# evlogger_voltage.net
KiCad netlist of a schematic drawn in EAGLE
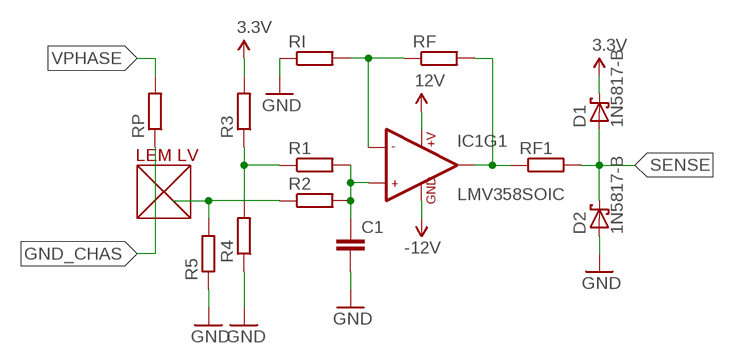
[diagram p0: schematic, sheet 1]

(export (version "E")
  (design (tool "Eeschema 10.0.6"))
  (components
    (comp (ref "C1")
      (value "C-EU025-024X044")
      (footprint "eagle-import:C025-024X044")
      (libsource (lib "eagle-import") (part "C-EU025-024X044"))
    )
    (comp (ref "D1")
      (value "1N5817-B")
      (footprint "eagle-import:DO41-7.6")
      (libsource (lib "eagle-import") (part "1N5817-B"))
    )
    (comp (ref "D2")
      (value "1N5817-B")
      (footprint "eagle-import:DO41-7.6")
      (libsource (lib "eagle-import") (part "1N5817-B"))
    )
    (comp (ref "IC1")
      (value "LMV358SOIC")
      (footprint "eagle-import:SO08")
      (libsource (lib "eagle-import") (part "LMV358SOIC"))
    )
    (comp (ref "R1")
      (value "R-EU_0207/10")
      (footprint "eagle-import:0207_10")
      (libsource (lib "eagle-import") (part "R-EU_0207/10"))
    )
    (comp (ref "R2")
      (value "R-EU_0207/10")
      (footprint "eagle-import:0207_10")
      (libsource (lib "eagle-import") (part "R-EU_0207/10"))
    )
    (comp (ref "R3")
      (value "R-EU_0207/10")
      (footprint "eagle-import:0207_10")
      (libsource (lib "eagle-import") (part "R-EU_0207/10"))
    )
    (comp (ref "R4")
      (value "R-EU_0207/10")
      (footprint "eagle-import:0207_10")
      (libsource (lib "eagle-import") (part "R-EU_0207/10"))
    )
    (comp (ref "R5")
      (value "R-EU_0207/10")
      (footprint "eagle-import:0207_10")
      (libsource (lib "eagle-import") (part "R-EU_0207/10"))
    )
    (comp (ref "RF")
      (value "R-EU_0207/10")
      (footprint "eagle-import:0207_10")
      (libsource (lib "eagle-import") (part "R-EU_0207/10"))
    )
    (comp (ref "RF1")
      (value "R-EU_0207/10")
      (footprint "eagle-import:0207_10")
      (libsource (lib "eagle-import") (part "R-EU_0207/10"))
    )
    (comp (ref "RI")
      (value "R-EU_0207/10")
      (footprint "eagle-import:0207_10")
      (libsource (lib "eagle-import") (part "R-EU_0207/10"))
    )
    (comp (ref "RP")
      (value "R-EU_0207/10")
      (footprint "eagle-import:0207_10")
      (libsource (lib "eagle-import") (part "R-EU_0207/10"))
    )
  )
  (nets
    (net (code "1") (name "-12V") (class "Default")
      (node (ref "IC1") (pin "4") (pinfunction "GND_4") (pintype "power_in"))
    )
    (net (code "2") (name "3.3V") (class "Default")
      (node (ref "D1") (pin "C") (pinfunction "C_C") (pintype "passive"))
      (node (ref "R3") (pin "2") (pinfunction "2_2") (pintype "passive"))
    )
    (net (code "3") (name "12V") (class "Default")
      (node (ref "IC1") (pin "8") (pinfunction "+V_8") (pintype "power_in"))
    )
    (net (code "4") (name "GND") (class "Default")
      (node (ref "C1") (pin "2") (pinfunction "2_2") (pintype "passive"))
      (node (ref "D2") (pin "A") (pinfunction "A_A") (pintype "passive"))
      (node (ref "R4") (pin "1") (pinfunction "1_1") (pintype "passive"))
      (node (ref "R5") (pin "1") (pinfunction "1_1") (pintype "passive"))
      (node (ref "RI") (pin "1") (pinfunction "1_1") (pintype "passive"))
    )
    (net (code "5") (name "GND_CHAS") (class "Default")
      (node (ref "RP") (pin "1") (pinfunction "1_1") (pintype "passive"))
    )
    (net (code "6") (name "Net-(IC1A-+IN1)") (class "Default")
      (node (ref "C1") (pin "1") (pinfunction "1_1") (pintype "passive"))
      (node (ref "IC1") (pin "3") (pinfunction "+IN1_3") (pintype "input"))
      (node (ref "R1") (pin "2") (pinfunction "2_2") (pintype "passive"))
      (node (ref "R2") (pin "2") (pinfunction "2_2") (pintype "passive"))
    )
    (net (code "7") (name "Net-(IC1A--IN1)") (class "Default")
      (node (ref "IC1") (pin "2") (pinfunction "-IN1_2") (pintype "input"))
      (node (ref "RF") (pin "1") (pinfunction "1_1") (pintype "passive"))
      (node (ref "RI") (pin "2") (pinfunction "2_2") (pintype "passive"))
    )
    (net (code "8") (name "Net-(IC1A-OUT1)") (class "Default")
      (node (ref "IC1") (pin "1") (pinfunction "OUT1_1") (pintype "output"))
      (node (ref "RF") (pin "2") (pinfunction "2_2") (pintype "passive"))
      (node (ref "RF1") (pin "1") (pinfunction "1_1") (pintype "passive"))
    )
    (net (code "9") (name "Net-(R1-Pad1)") (class "Default")
      (node (ref "R1") (pin "1") (pinfunction "1_1") (pintype "passive"))
      (node (ref "R3") (pin "1") (pinfunction "1_1") (pintype "passive"))
      (node (ref "R4") (pin "2") (pinfunction "2_2") (pintype "passive"))
    )
    (net (code "10") (name "Net-(R2-Pad1)") (class "Default")
      (node (ref "R2") (pin "1") (pinfunction "1_1") (pintype "passive"))
      (node (ref "R5") (pin "2") (pinfunction "2_2") (pintype "passive"))
    )
    (net (code "11") (name "SENSE") (class "Default")
      (node (ref "D1") (pin "A") (pinfunction "A_A") (pintype "passive"))
      (node (ref "D2") (pin "C") (pinfunction "C_C") (pintype "passive"))
      (node (ref "RF1") (pin "2") (pinfunction "2_2") (pintype "passive"))
    )
    (net (code "12") (name "VPHASE") (class "Default")
      (node (ref "RP") (pin "2") (pinfunction "2_2") (pintype "passive"))
    )
  )
)
